# Differential_Signal_Generator.net
KiCad netlist of a schematic drawn in Altium Designer
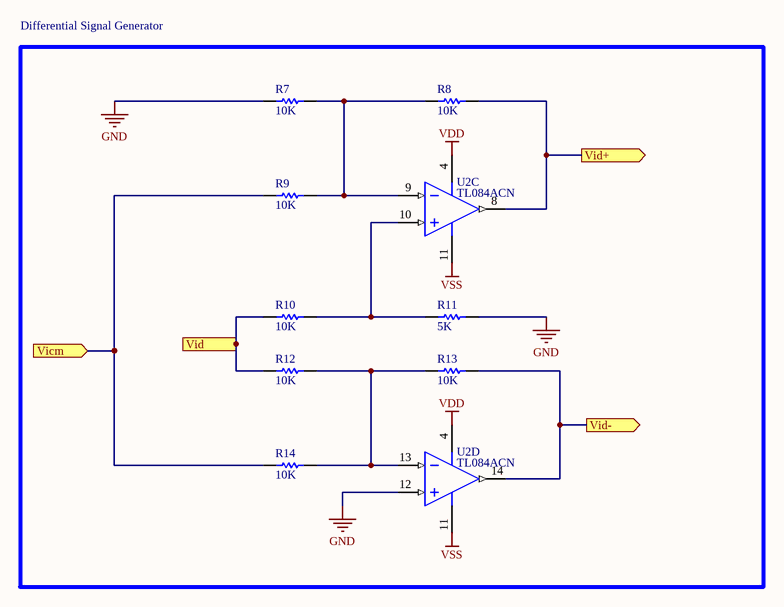
[diagram p0: Differential_Signal_Generator.SchDoc]

(export (version "E")
  (design (tool "Eeschema 10.0.6"))
  (components
    (comp (ref "R7")
      (value "10K")
      (footprint "Resistor_Axial 0.4")
      (description "Resistor")
      (fields (field (name "Comment") "Res1") (field (name "PUBLISHER") "Altium Limited"))
      (libsource (lib "signal-generator") (part "Res1"))
    )
    (comp (ref "R8")
      (value "10K")
      (footprint "Resistor_Axial 0.4")
      (description "Resistor")
      (fields (field (name "Comment") "Res1") (field (name "PUBLISHER") "Altium Limited"))
      (libsource (lib "signal-generator") (part "Res1"))
    )
    (comp (ref "R9")
      (value "10K")
      (footprint "Resistor_Axial 0.4")
      (description "Resistor")
      (fields (field (name "Comment") "Res1") (field (name "PUBLISHER") "Altium Limited"))
      (libsource (lib "signal-generator") (part "Res1"))
    )
    (comp (ref "R10")
      (value "10K")
      (footprint "Resistor_Axial 0.4")
      (description "Resistor")
      (fields (field (name "Comment") "Res1") (field (name "PUBLISHER") "Altium Limited"))
      (libsource (lib "signal-generator") (part "Res1"))
    )
    (comp (ref "R11")
      (value "5K")
      (footprint "Resistor_Axial 0.4")
      (description "Resistor")
      (fields (field (name "Comment") "Res1") (field (name "PUBLISHER") "Altium Limited"))
      (libsource (lib "signal-generator") (part "Res1"))
    )
    (comp (ref "R12")
      (value "10K")
      (footprint "Resistor_Axial 0.4")
      (description "Resistor")
      (fields (field (name "Comment") "Res1") (field (name "PUBLISHER") "Altium Limited"))
      (libsource (lib "signal-generator") (part "Res1"))
    )
    (comp (ref "R13")
      (value "10K")
      (footprint "Resistor_Axial 0.4")
      (description "Resistor")
      (fields (field (name "Comment") "Res1") (field (name "PUBLISHER") "Altium Limited"))
      (libsource (lib "signal-generator") (part "Res1"))
    )
    (comp (ref "R14")
      (value "10K")
      (footprint "Resistor_Axial 0.4")
      (description "Resistor")
      (fields (field (name "Comment") "Res1") (field (name "PUBLISHER") "Altium Limited"))
      (libsource (lib "signal-generator") (part "Res1"))
    )
    (comp (ref "U2")
      (value "TL084ACN")
      (footprint "N0014A")
      (description "JFET-Input Operational Amplifier, 7 to 36 V, 0 to 70 degC, 14-pin DIP (N14), Pb-Free (RoHS)")
      (fields (field (name "MANUFACTURER") "Texas Instruments"))
      (libsource (lib "Altium Content Vault") (part "TI-TLXX4X_MC3403-X14"))
    )
  )
  (nets
    (net (code "1") (name "/Vicm") (class "Default")
      (node (ref "R14") (pin "1") (pinfunction "1_1") (pintype "passive"))
      (node (ref "R9") (pin "1") (pinfunction "1_1") (pintype "passive"))
    )
    (net (code "2") (name "/Vid") (class "Default")
      (node (ref "R10") (pin "1") (pinfunction "1_1") (pintype "passive"))
      (node (ref "R12") (pin "1") (pinfunction "1_1") (pintype "passive"))
    )
    (net (code "3") (name "/Vid+") (class "Default")
      (node (ref "R8") (pin "2") (pinfunction "2_2") (pintype "passive"))
      (node (ref "U2") (pin "8") (pinfunction "OUT3_8") (pintype "output"))
    )
    (net (code "4") (name "/Vid-") (class "Default")
      (node (ref "R13") (pin "2") (pinfunction "2_2") (pintype "passive"))
      (node (ref "U2") (pin "14") (pinfunction "OUT4_14") (pintype "output"))
    )
    (net (code "5") (name "GND") (class "Default")
      (node (ref "R11") (pin "2") (pinfunction "2_2") (pintype "passive"))
      (node (ref "R7") (pin "1") (pinfunction "1_1") (pintype "passive"))
      (node (ref "U2") (pin "12") (pinfunction "IN4+_12") (pintype "input"))
    )
    (net (code "6") (name "Net-(U2C-IN3+)") (class "Default")
      (node (ref "R10") (pin "2") (pinfunction "2_2") (pintype "passive"))
      (node (ref "R11") (pin "1") (pinfunction "1_1") (pintype "passive"))
      (node (ref "U2") (pin "10") (pinfunction "IN3+_10") (pintype "input"))
    )
    (net (code "7") (name "Net-(U2C-IN3-)") (class "Default")
      (node (ref "R7") (pin "2") (pinfunction "2_2") (pintype "passive"))
      (node (ref "R8") (pin "1") (pinfunction "1_1") (pintype "passive"))
      (node (ref "R9") (pin "2") (pinfunction "2_2") (pintype "passive"))
      (node (ref "U2") (pin "9") (pinfunction "IN3-_9") (pintype "input"))
    )
    (net (code "8") (name "Net-(U2D-IN4-)") (class "Default")
      (node (ref "R12") (pin "2") (pinfunction "2_2") (pintype "passive"))
      (node (ref "R13") (pin "1") (pinfunction "1_1") (pintype "passive"))
      (node (ref "R14") (pin "2") (pinfunction "2_2") (pintype "passive"))
      (node (ref "U2") (pin "13") (pinfunction "IN4-_13") (pintype "input"))
    )
    (net (code "9") (name "VDD") (class "Default")
      (node (ref "U2") (pin "4") (pinfunction "VCC+_4") (pintype "power_in"))
    )
    (net (code "10") (name "VSS") (class "Default")
      (node (ref "U2") (pin "11") (pinfunction "VCC-_11") (pintype "power_in"))
    )
  )
)
